# SD_Card.net
KiCad netlist of a schematic drawn in Altium Designer
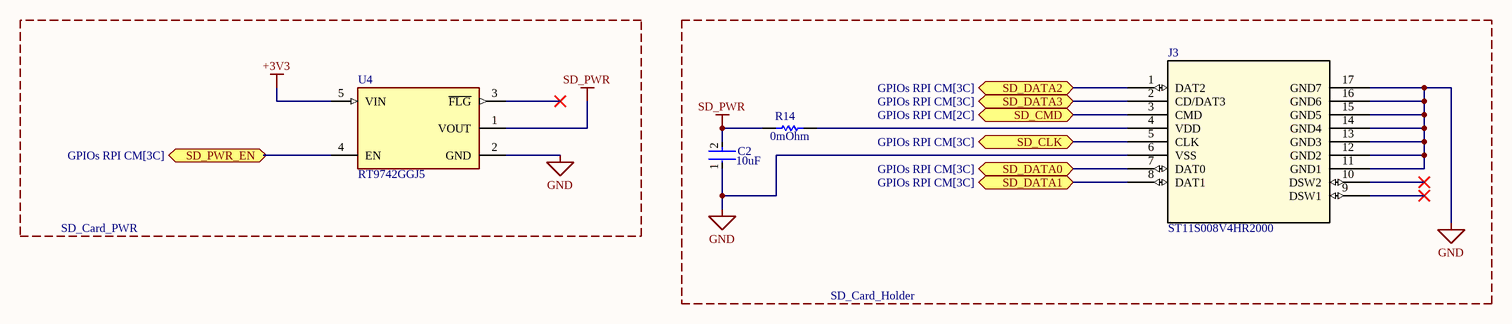
[diagram p0: SD Card.SchDoc]

(export (version "E")
  (design (tool "Eeschema 10.0.6"))
  (components
    (comp (ref "C2")
      (value "C1608X5R1A106K080AC")
      (footprint "FP-C1608-080-0_1-MFG")
      (description "Multilayer Ceramic Capacitors 10μF ±10% 10V X5R SMD 0603")
      (fields
        (field (name "VOLTAGE") "10V")
        (field (name "TOLERANCE") "10%")
        (field (name "CAPACITANCE") "10uF")
      )
      (libsource (lib "Altium Content Vault") (part "236180d848d6139a670b325ea6854c9"))
    )
    (comp (ref "J3")
      (value "ST11S008V4HR2000")
      (footprint "ST11S008V4HR2000_JAE")
      (description "SD Card")
      (libsource (lib "Compute Module 5 ") (part "ST11S008V4HR2000"))
    )
    (comp (ref "R14")
      (value "ERJ2GE0R00X")
      (footprint "RESC1005X40X25LL05T05")
      (description "Chip Resistor, 0 Ohm, 0.1 W, -55 to 155 degC, 0402 (1005 Metric), RoHS, Tape and Reel")
      (fields
        (field (name "MANUFACTURER") "Panasonic")
        (field (name "RESISTANCE") "0mOhm")
        (field (name "TOLERANCE") "5%")
      )
      (libsource (lib "Altium Content Vault") (part "RES-2"))
    )
    (comp (ref "U4")
      (value "RT9742GGJ5")
      (footprint "FP-RT9742GGJ5-IPC_C")
      (description "IC PWR SWTCH N-CHAN 1:1 TSOT23-5")
      (libsource (lib "Altium Content Vault") (part "6b3db7b45087fee8fb60b49bef92a32"))
    )
  )
  (nets
    (net (code "1") (name "+3V3") (class "Default")
      (node (ref "U4") (pin "5") (pinfunction "VIN_5") (pintype "input"))
    )
    (net (code "2") (name "/SD_CLK") (class "Default")
      (node (ref "J3") (pin "5") (pinfunction "CLK_5") (pintype "passive"))
    )
    (net (code "3") (name "/SD_CMD") (class "Default")
      (node (ref "J3") (pin "3") (pinfunction "CMD_3") (pintype "passive"))
    )
    (net (code "4") (name "/SD_DATA0") (class "Default")
      (node (ref "J3") (pin "7") (pinfunction "DAT0_7") (pintype "bidirectional"))
    )
    (net (code "5") (name "/SD_DATA1") (class "Default")
      (node (ref "J3") (pin "8") (pinfunction "DAT1_8") (pintype "bidirectional"))
    )
    (net (code "6") (name "/SD_DATA2") (class "Default")
      (node (ref "J3") (pin "1") (pinfunction "DAT2_1") (pintype "bidirectional"))
    )
    (net (code "7") (name "/SD_DATA3") (class "Default")
      (node (ref "J3") (pin "2") (pinfunction "CD/DAT3_2") (pintype "passive"))
    )
    (net (code "8") (name "/SD_PWR_EN") (class "Default")
      (node (ref "U4") (pin "4") (pinfunction "EN_4") (pintype "passive"))
    )
    (net (code "9") (name "GND") (class "Default")
      (node (ref "C2") (pin "1") (pinfunction "1_1") (pintype "passive"))
      (node (ref "J3") (pin "11") (pinfunction "GND1_11") (pintype "power_in"))
      (node (ref "J3") (pin "12") (pinfunction "GND2_12") (pintype "power_in"))
      (node (ref "J3") (pin "13") (pinfunction "GND3_13") (pintype "power_in"))
      (node (ref "J3") (pin "14") (pinfunction "GND4_14") (pintype "power_in"))
      (node (ref "J3") (pin "15") (pinfunction "GND5_15") (pintype "power_in"))
      (node (ref "J3") (pin "16") (pinfunction "GND6_16") (pintype "power_in"))
      (node (ref "J3") (pin "17") (pinfunction "GND7_17") (pintype "power_in"))
      (node (ref "J3") (pin "6") (pinfunction "VSS_6") (pintype "power_in"))
      (node (ref "U4") (pin "2") (pinfunction "GND_2") (pintype "power_in"))
    )
    (net (code "10") (name "Net-(J3-VDD)") (class "Default")
      (node (ref "J3") (pin "4") (pinfunction "VDD_4") (pintype "power_in"))
      (node (ref "R14") (pin "2") (pinfunction "2_2") (pintype "passive"))
    )
    (net (code "11") (name "SD_PWR") (class "Default")
      (node (ref "C2") (pin "2") (pinfunction "2_2") (pintype "passive"))
      (node (ref "R14") (pin "1") (pinfunction "1_1") (pintype "passive"))
      (node (ref "U4") (pin "1") (pinfunction "VOUT_1") (pintype "power_in"))
    )
    (net (code "12") (name "unconnected-(J3-DSW1-Pad9)") (class "Default")
      (node (ref "J3") (pin "9") (pinfunction "DSW1_9") (pintype "bidirectional+no_connect"))
    )
    (net (code "13") (name "unconnected-(J3-DSW2-Pad10)") (class "Default")
      (node (ref "J3") (pin "10") (pinfunction "DSW2_10") (pintype "bidirectional+no_connect"))
    )
    (net (code "14") (name "unconnected-(U4-~{FLG}-Pad3)") (class "Default")
      (node (ref "U4") (pin "3") (pinfunction "~{FLG}_3") (pintype "output+no_connect"))
    )
  )
)
